# PCB.net
KiCad netlist of a schematic drawn in EAGLE
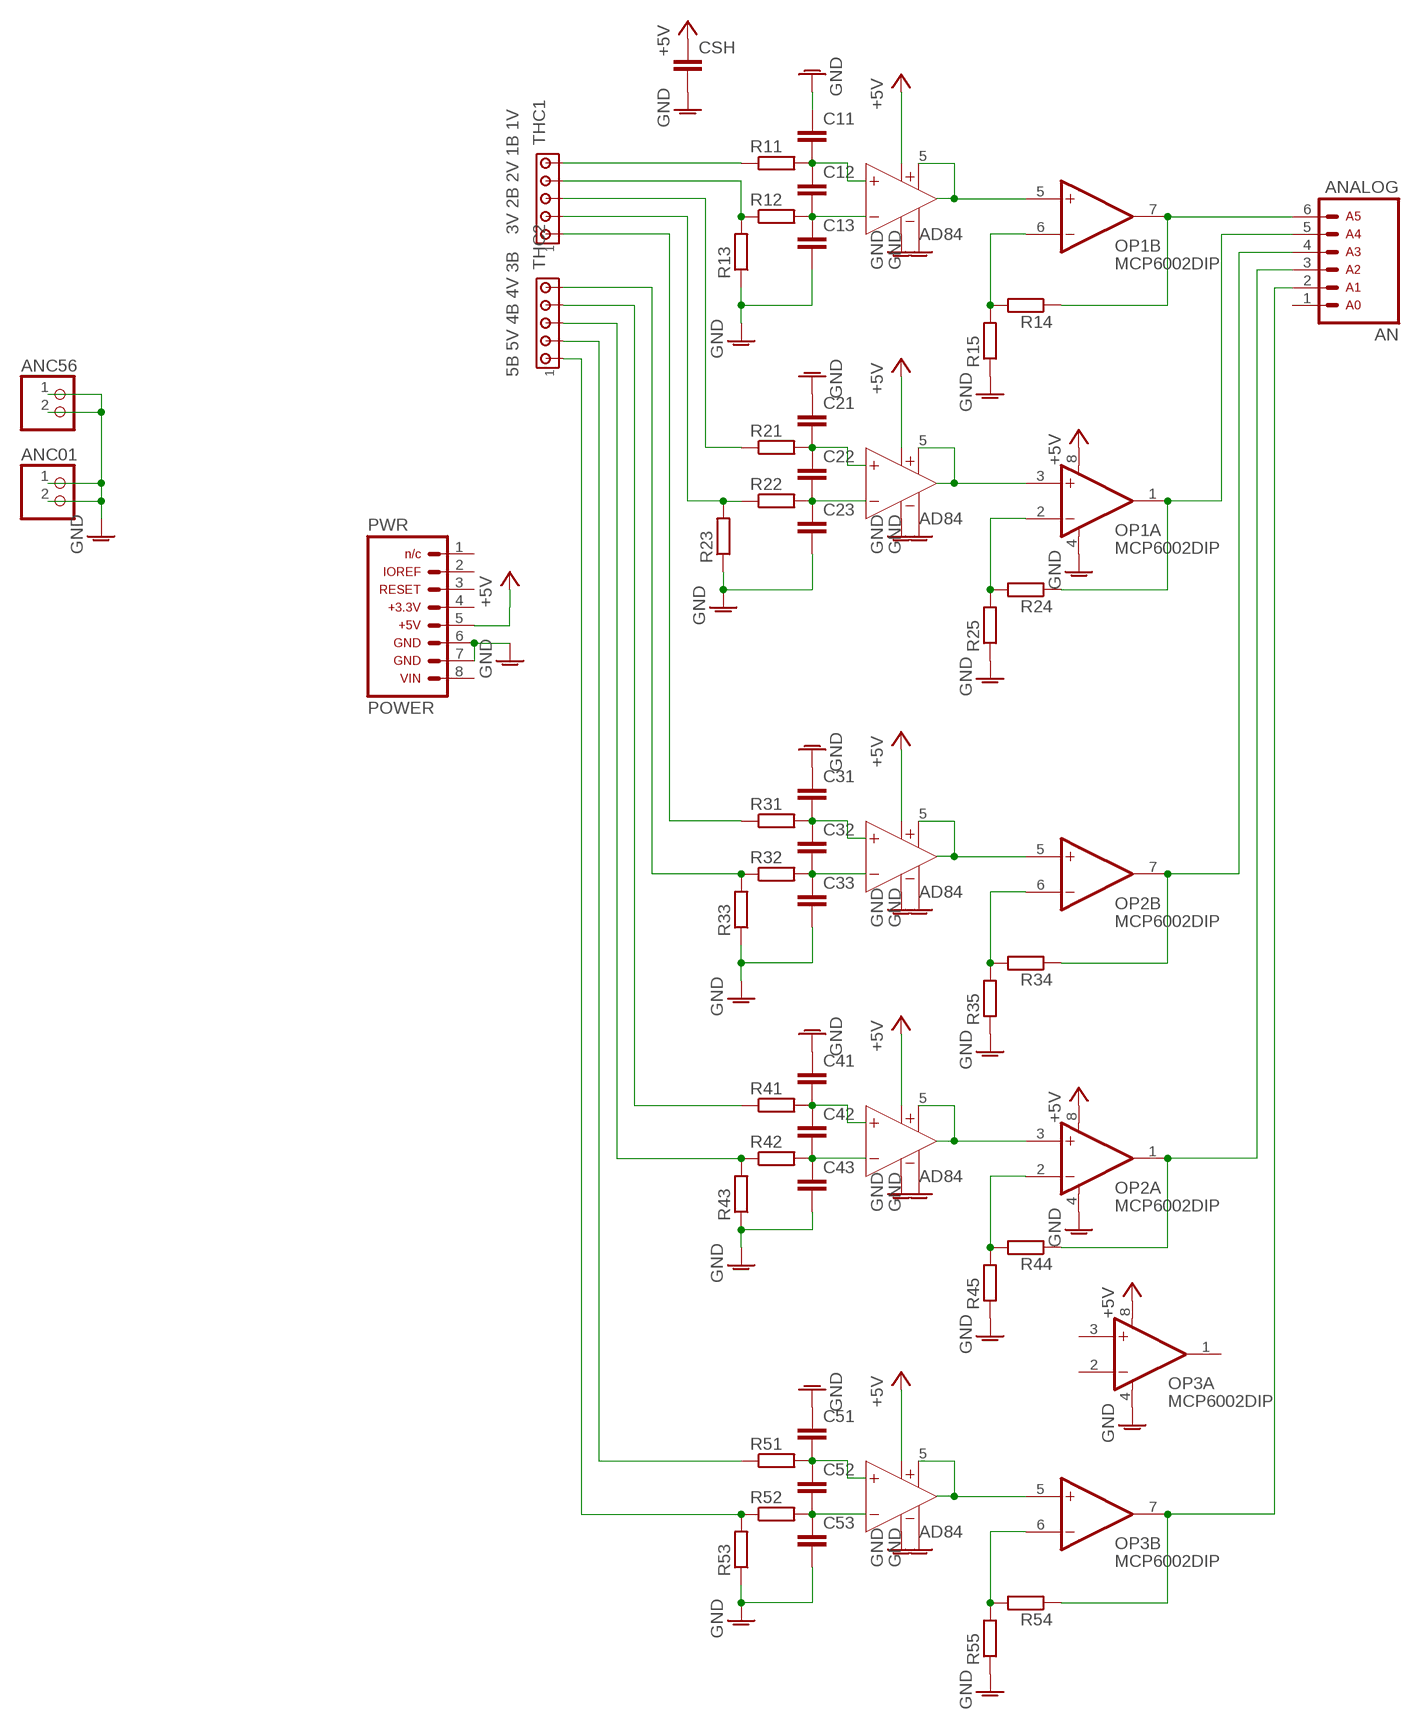
[diagram p0: schematic, sheet 1]

(export (version "E")
  (design (tool "Eeschema 10.0.6"))
  (components
    (comp (ref "AN")
      (value "ARDUINO_CONN-ANALOGSIP")
      (footprint "eagle-import:CONN-1X06")
      (libsource (lib "eagle-import") (part "ARDUINO_CONN-ANALOGSIP"))
    )
    (comp (ref "ANC01")
      (value "PINHD-1X2")
      (footprint "eagle-import:1X02")
      (libsource (lib "eagle-import") (part "PINHD-1X2"))
    )
    (comp (ref "ANC56")
      (value "PINHD-1X2")
      (footprint "eagle-import:1X02")
      (libsource (lib "eagle-import") (part "PINHD-1X2"))
    )
    (comp (ref "C11")
      (value "C-EU050-025X075")
      (footprint "eagle-import:C050-025X075")
      (libsource (lib "eagle-import") (part "C-EU050-025X075"))
    )
    (comp (ref "C12")
      (value "C-EU050-025X075")
      (footprint "eagle-import:C050-025X075")
      (libsource (lib "eagle-import") (part "C-EU050-025X075"))
    )
    (comp (ref "C13")
      (value "C-EU050-025X075")
      (footprint "eagle-import:C050-025X075")
      (libsource (lib "eagle-import") (part "C-EU050-025X075"))
    )
    (comp (ref "C21")
      (value "C-EU050-025X075")
      (footprint "eagle-import:C050-025X075")
      (libsource (lib "eagle-import") (part "C-EU050-025X075"))
    )
    (comp (ref "C22")
      (value "C-EU050-025X075")
      (footprint "eagle-import:C050-025X075")
      (libsource (lib "eagle-import") (part "C-EU050-025X075"))
    )
    (comp (ref "C23")
      (value "C-EU050-025X075")
      (footprint "eagle-import:C050-025X075")
      (libsource (lib "eagle-import") (part "C-EU050-025X075"))
    )
    (comp (ref "C31")
      (value "C-EU050-025X075")
      (footprint "eagle-import:C050-025X075")
      (libsource (lib "eagle-import") (part "C-EU050-025X075"))
    )
    (comp (ref "C32")
      (value "C-EU050-025X075")
      (footprint "eagle-import:C050-025X075")
      (libsource (lib "eagle-import") (part "C-EU050-025X075"))
    )
    (comp (ref "C33")
      (value "C-EU050-025X075")
      (footprint "eagle-import:C050-025X075")
      (libsource (lib "eagle-import") (part "C-EU050-025X075"))
    )
    (comp (ref "C41")
      (value "C-EU050-025X075")
      (footprint "eagle-import:C050-025X075")
      (libsource (lib "eagle-import") (part "C-EU050-025X075"))
    )
    (comp (ref "C42")
      (value "C-EU050-025X075")
      (footprint "eagle-import:C050-025X075")
      (libsource (lib "eagle-import") (part "C-EU050-025X075"))
    )
    (comp (ref "C43")
      (value "C-EU050-025X075")
      (footprint "eagle-import:C050-025X075")
      (libsource (lib "eagle-import") (part "C-EU050-025X075"))
    )
    (comp (ref "C51")
      (value "C-EU050-025X075")
      (footprint "eagle-import:C050-025X075")
      (libsource (lib "eagle-import") (part "C-EU050-025X075"))
    )
    (comp (ref "C52")
      (value "C-EU050-025X075")
      (footprint "eagle-import:C050-025X075")
      (libsource (lib "eagle-import") (part "C-EU050-025X075"))
    )
    (comp (ref "C53")
      (value "C-EU050-025X075")
      (footprint "eagle-import:C050-025X075")
      (libsource (lib "eagle-import") (part "C-EU050-025X075"))
    )
    (comp (ref "CSH")
      (value "C-EU050-025X075")
      (footprint "eagle-import:C050-025X075")
      (libsource (lib "eagle-import") (part "C-EU050-025X075"))
    )
    (comp (ref "OP1")
      (value "MCP6002DIP")
      (footprint "eagle-import:DIP-8")
      (libsource (lib "eagle-import") (part "MCP6002DIP"))
    )
    (comp (ref "OP2")
      (value "MCP6002DIP")
      (footprint "eagle-import:DIP-8")
      (libsource (lib "eagle-import") (part "MCP6002DIP"))
    )
    (comp (ref "OP3")
      (value "MCP6002DIP")
      (footprint "eagle-import:DIP-8")
      (libsource (lib "eagle-import") (part "MCP6002DIP"))
    )
    (comp (ref "PWR")
      (value "ARDUINO_CONN-POWERSIP")
      (footprint "eagle-import:CONN-1X08")
      (libsource (lib "eagle-import") (part "ARDUINO_CONN-POWERSIP"))
    )
    (comp (ref "R11")
      (value "R-EU_0207/10")
      (footprint "eagle-import:0207_10")
      (libsource (lib "eagle-import") (part "R-EU_0207/10"))
    )
    (comp (ref "R12")
      (value "R-EU_0207/10")
      (footprint "eagle-import:0207_10")
      (libsource (lib "eagle-import") (part "R-EU_0207/10"))
    )
    (comp (ref "R13")
      (value "R-EU_0207/10")
      (footprint "eagle-import:0207_10")
      (libsource (lib "eagle-import") (part "R-EU_0207/10"))
    )
    (comp (ref "R14")
      (value "R-EU_0207/10")
      (footprint "eagle-import:0207_10")
      (libsource (lib "eagle-import") (part "R-EU_0207/10"))
    )
    (comp (ref "R15")
      (value "R-EU_0207/10")
      (footprint "eagle-import:0207_10")
      (libsource (lib "eagle-import") (part "R-EU_0207/10"))
    )
    (comp (ref "R21")
      (value "R-EU_0207/10")
      (footprint "eagle-import:0207_10")
      (libsource (lib "eagle-import") (part "R-EU_0207/10"))
    )
    (comp (ref "R22")
      (value "R-EU_0207/10")
      (footprint "eagle-import:0207_10")
      (libsource (lib "eagle-import") (part "R-EU_0207/10"))
    )
    (comp (ref "R23")
      (value "R-EU_0207/10")
      (footprint "eagle-import:0207_10")
      (libsource (lib "eagle-import") (part "R-EU_0207/10"))
    )
    (comp (ref "R24")
      (value "R-EU_0207/10")
      (footprint "eagle-import:0207_10")
      (libsource (lib "eagle-import") (part "R-EU_0207/10"))
    )
    (comp (ref "R25")
      (value "R-EU_0207/10")
      (footprint "eagle-import:0207_10")
      (libsource (lib "eagle-import") (part "R-EU_0207/10"))
    )
    (comp (ref "R31")
      (value "R-EU_0207/10")
      (footprint "eagle-import:0207_10")
      (libsource (lib "eagle-import") (part "R-EU_0207/10"))
    )
    (comp (ref "R32")
      (value "R-EU_0207/10")
      (footprint "eagle-import:0207_10")
      (libsource (lib "eagle-import") (part "R-EU_0207/10"))
    )
    (comp (ref "R33")
      (value "R-EU_0207/10")
      (footprint "eagle-import:0207_10")
      (libsource (lib "eagle-import") (part "R-EU_0207/10"))
    )
    (comp (ref "R34")
      (value "R-EU_0207/10")
      (footprint "eagle-import:0207_10")
      (libsource (lib "eagle-import") (part "R-EU_0207/10"))
    )
    (comp (ref "R35")
      (value "R-EU_0207/10")
      (footprint "eagle-import:0207_10")
      (libsource (lib "eagle-import") (part "R-EU_0207/10"))
    )
    (comp (ref "R41")
      (value "R-EU_0207/10")
      (footprint "eagle-import:0207_10")
      (libsource (lib "eagle-import") (part "R-EU_0207/10"))
    )
    (comp (ref "R42")
      (value "R-EU_0207/10")
      (footprint "eagle-import:0207_10")
      (libsource (lib "eagle-import") (part "R-EU_0207/10"))
    )
    (comp (ref "R43")
      (value "R-EU_0207/10")
      (footprint "eagle-import:0207_10")
      (libsource (lib "eagle-import") (part "R-EU_0207/10"))
    )
    (comp (ref "R44")
      (value "R-EU_0207/10")
      (footprint "eagle-import:0207_10")
      (libsource (lib "eagle-import") (part "R-EU_0207/10"))
    )
    (comp (ref "R45")
      (value "R-EU_0207/10")
      (footprint "eagle-import:0207_10")
      (libsource (lib "eagle-import") (part "R-EU_0207/10"))
    )
    (comp (ref "R51")
      (value "R-EU_0207/10")
      (footprint "eagle-import:0207_10")
      (libsource (lib "eagle-import") (part "R-EU_0207/10"))
    )
    (comp (ref "R52")
      (value "R-EU_0207/10")
      (footprint "eagle-import:0207_10")
      (libsource (lib "eagle-import") (part "R-EU_0207/10"))
    )
    (comp (ref "R53")
      (value "R-EU_0207/10")
      (footprint "eagle-import:0207_10")
      (libsource (lib "eagle-import") (part "R-EU_0207/10"))
    )
    (comp (ref "R54")
      (value "R-EU_0207/10")
      (footprint "eagle-import:0207_10")
      (libsource (lib "eagle-import") (part "R-EU_0207/10"))
    )
    (comp (ref "R55")
      (value "R-EU_0207/10")
      (footprint "eagle-import:0207_10")
      (libsource (lib "eagle-import") (part "R-EU_0207/10"))
    )
    (comp (ref "THC1")
      (value "3V 2B 2V 1B 1V")
      (footprint "eagle-import:10X05MTA")
      (libsource (lib "eagle-import") (part "MTA05-100"))
    )
    (comp (ref "THC2")
      (value "5B 5V 4B 4V 3B")
      (footprint "eagle-import:10X05MTA")
      (libsource (lib "eagle-import") (part "MTA05-100"))
    )
    (comp (ref "U$1")
      (value "AD84")
      (footprint "eagle-import:DIP-8")
      (libsource (lib "eagle-import") (part "AD84"))
    )
    (comp (ref "U$2")
      (value "AD84")
      (footprint "eagle-import:DIP-8")
      (libsource (lib "eagle-import") (part "AD84"))
    )
    (comp (ref "U$3")
      (value "AD84")
      (footprint "eagle-import:DIP-8")
      (libsource (lib "eagle-import") (part "AD84"))
    )
    (comp (ref "U$4")
      (value "AD84")
      (footprint "eagle-import:DIP-8")
      (libsource (lib "eagle-import") (part "AD84"))
    )
    (comp (ref "U$5")
      (value "AD84")
      (footprint "eagle-import:DIP-8")
      (libsource (lib "eagle-import") (part "AD84"))
    )
  )
  (nets
    (net (code "1") (name "+5V") (class "Default")
      (node (ref "CSH") (pin "1") (pinfunction "1_1") (pintype "passive"))
      (node (ref "OP1") (pin "8") (pinfunction "V+_8") (pintype "power_in"))
      (node (ref "OP2") (pin "8") (pinfunction "V+_8") (pintype "power_in"))
      (node (ref "OP3") (pin "8") (pinfunction "V+_8") (pintype "power_in"))
      (node (ref "PWR") (pin "5") (pinfunction "5_5") (pintype "passive"))
      (node (ref "U$1") (pin "7") (pinfunction "V+_7") (pintype "power_in"))
      (node (ref "U$2") (pin "7") (pinfunction "V+_7") (pintype "power_in"))
      (node (ref "U$3") (pin "7") (pinfunction "V+_7") (pintype "power_in"))
      (node (ref "U$4") (pin "7") (pinfunction "V+_7") (pintype "power_in"))
      (node (ref "U$5") (pin "7") (pinfunction "V+_7") (pintype "power_in"))
    )
    (net (code "2") (name "GND") (class "Default")
      (node (ref "ANC01") (pin "1") (pinfunction "1_1") (pintype "passive"))
      (node (ref "ANC01") (pin "2") (pinfunction "2_2") (pintype "passive"))
      (node (ref "ANC56") (pin "1") (pinfunction "1_1") (pintype "passive"))
      (node (ref "ANC56") (pin "2") (pinfunction "2_2") (pintype "passive"))
      (node (ref "C11") (pin "1") (pinfunction "1_1") (pintype "passive"))
      (node (ref "C13") (pin "2") (pinfunction "2_2") (pintype "passive"))
      (node (ref "C21") (pin "1") (pinfunction "1_1") (pintype "passive"))
      (node (ref "C23") (pin "2") (pinfunction "2_2") (pintype "passive"))
      (node (ref "C31") (pin "1") (pinfunction "1_1") (pintype "passive"))
      (node (ref "C33") (pin "2") (pinfunction "2_2") (pintype "passive"))
      (node (ref "C41") (pin "1") (pinfunction "1_1") (pintype "passive"))
      (node (ref "C43") (pin "2") (pinfunction "2_2") (pintype "passive"))
      (node (ref "C51") (pin "1") (pinfunction "1_1") (pintype "passive"))
      (node (ref "C53") (pin "2") (pinfunction "2_2") (pintype "passive"))
      (node (ref "CSH") (pin "2") (pinfunction "2_2") (pintype "passive"))
      (node (ref "OP1") (pin "4") (pinfunction "V-_4") (pintype "power_in"))
      (node (ref "OP2") (pin "4") (pinfunction "V-_4") (pintype "power_in"))
      (node (ref "OP3") (pin "4") (pinfunction "V-_4") (pintype "power_in"))
      (node (ref "PWR") (pin "6") (pinfunction "6_6") (pintype "passive"))
      (node (ref "PWR") (pin "7") (pinfunction "7_7") (pintype "passive"))
      (node (ref "R13") (pin "1") (pinfunction "1_1") (pintype "passive"))
      (node (ref "R15") (pin "1") (pinfunction "1_1") (pintype "passive"))
      (node (ref "R23") (pin "1") (pinfunction "1_1") (pintype "passive"))
      (node (ref "R25") (pin "1") (pinfunction "1_1") (pintype "passive"))
      (node (ref "R33") (pin "1") (pinfunction "1_1") (pintype "passive"))
      (node (ref "R35") (pin "1") (pinfunction "1_1") (pintype "passive"))
      (node (ref "R43") (pin "1") (pinfunction "1_1") (pintype "passive"))
      (node (ref "R45") (pin "1") (pinfunction "1_1") (pintype "passive"))
      (node (ref "R53") (pin "1") (pinfunction "1_1") (pintype "passive"))
      (node (ref "R55") (pin "1") (pinfunction "1_1") (pintype "passive"))
      (node (ref "U$1") (pin "2") (pinfunction "REF_2") (pintype "passive"))
      (node (ref "U$1") (pin "3") (pinfunction "V-_3") (pintype "power_in"))
      (node (ref "U$2") (pin "2") (pinfunction "REF_2") (pintype "passive"))
      (node (ref "U$2") (pin "3") (pinfunction "V-_3") (pintype "power_in"))
      (node (ref "U$3") (pin "2") (pinfunction "REF_2") (pintype "passive"))
      (node (ref "U$3") (pin "3") (pinfunction "V-_3") (pintype "power_in"))
      (node (ref "U$4") (pin "2") (pinfunction "REF_2") (pintype "passive"))
      (node (ref "U$4") (pin "3") (pinfunction "V-_3") (pintype "power_in"))
      (node (ref "U$5") (pin "2") (pinfunction "REF_2") (pintype "passive"))
      (node (ref "U$5") (pin "3") (pinfunction "V-_3") (pintype "power_in"))
    )
    (net (code "3") (name "Net-(OP1A-+IN)") (class "Default")
      (node (ref "OP1") (pin "3") (pinfunction "+IN_3") (pintype "input"))
      (node (ref "U$2") (pin "5") (pinfunction "SENS_5") (pintype "output"))
      (node (ref "U$2") (pin "6") (pinfunction "OUT_6") (pintype "output"))
    )
    (net (code "4") (name "Net-(OP1A--IN)") (class "Default")
      (node (ref "OP1") (pin "2") (pinfunction "-IN_2") (pintype "input"))
      (node (ref "R24") (pin "2") (pinfunction "2_2") (pintype "passive"))
      (node (ref "R25") (pin "2") (pinfunction "2_2") (pintype "passive"))
    )
    (net (code "5") (name "Net-(OP1A-OUT)") (class "Default")
      (node (ref "AN") (pin "5") (pinfunction "5_5") (pintype "passive"))
      (node (ref "OP1") (pin "1") (pinfunction "OUT_1") (pintype "output"))
      (node (ref "R24") (pin "1") (pinfunction "1_1") (pintype "passive"))
    )
    (net (code "6") (name "Net-(OP1B-+IN)") (class "Default")
      (node (ref "OP1") (pin "5") (pinfunction "+IN_5") (pintype "input"))
      (node (ref "U$1") (pin "5") (pinfunction "SENS_5") (pintype "output"))
      (node (ref "U$1") (pin "6") (pinfunction "OUT_6") (pintype "output"))
    )
    (net (code "7") (name "Net-(OP1B--IN)") (class "Default")
      (node (ref "OP1") (pin "6") (pinfunction "-IN_6") (pintype "input"))
      (node (ref "R14") (pin "2") (pinfunction "2_2") (pintype "passive"))
      (node (ref "R15") (pin "2") (pinfunction "2_2") (pintype "passive"))
    )
    (net (code "8") (name "Net-(OP1B-OUT)") (class "Default")
      (node (ref "AN") (pin "6") (pinfunction "6_6") (pintype "passive"))
      (node (ref "OP1") (pin "7") (pinfunction "OUT_7") (pintype "output"))
      (node (ref "R14") (pin "1") (pinfunction "1_1") (pintype "passive"))
    )
    (net (code "9") (name "Net-(OP2A-+IN)") (class "Default")
      (node (ref "OP2") (pin "3") (pinfunction "+IN_3") (pintype "input"))
      (node (ref "U$4") (pin "5") (pinfunction "SENS_5") (pintype "output"))
      (node (ref "U$4") (pin "6") (pinfunction "OUT_6") (pintype "output"))
    )
    (net (code "10") (name "Net-(OP2A--IN)") (class "Default")
      (node (ref "OP2") (pin "2") (pinfunction "-IN_2") (pintype "input"))
      (node (ref "R44") (pin "2") (pinfunction "2_2") (pintype "passive"))
      (node (ref "R45") (pin "2") (pinfunction "2_2") (pintype "passive"))
    )
    (net (code "11") (name "Net-(OP2A-OUT)") (class "Default")
      (node (ref "AN") (pin "3") (pinfunction "3_3") (pintype "passive"))
      (node (ref "OP2") (pin "1") (pinfunction "OUT_1") (pintype "output"))
      (node (ref "R44") (pin "1") (pinfunction "1_1") (pintype "passive"))
    )
    (net (code "12") (name "Net-(OP2B-+IN)") (class "Default")
      (node (ref "OP2") (pin "5") (pinfunction "+IN_5") (pintype "input"))
      (node (ref "U$3") (pin "5") (pinfunction "SENS_5") (pintype "output"))
      (node (ref "U$3") (pin "6") (pinfunction "OUT_6") (pintype "output"))
    )
    (net (code "13") (name "Net-(OP2B--IN)") (class "Default")
      (node (ref "OP2") (pin "6") (pinfunction "-IN_6") (pintype "input"))
      (node (ref "R34") (pin "2") (pinfunction "2_2") (pintype "passive"))
      (node (ref "R35") (pin "2") (pinfunction "2_2") (pintype "passive"))
    )
    (net (code "14") (name "Net-(OP2B-OUT)") (class "Default")
      (node (ref "AN") (pin "4") (pinfunction "4_4") (pintype "passive"))
      (node (ref "OP2") (pin "7") (pinfunction "OUT_7") (pintype "output"))
      (node (ref "R34") (pin "1") (pinfunction "1_1") (pintype "passive"))
    )
    (net (code "15") (name "Net-(OP3B-+IN)") (class "Default")
      (node (ref "OP3") (pin "5") (pinfunction "+IN_5") (pintype "input"))
      (node (ref "U$5") (pin "5") (pinfunction "SENS_5") (pintype "output"))
      (node (ref "U$5") (pin "6") (pinfunction "OUT_6") (pintype "output"))
    )
    (net (code "16") (name "Net-(OP3B--IN)") (class "Default")
      (node (ref "OP3") (pin "6") (pinfunction "-IN_6") (pintype "input"))
      (node (ref "R54") (pin "2") (pinfunction "2_2") (pintype "passive"))
      (node (ref "R55") (pin "2") (pinfunction "2_2") (pintype "passive"))
    )
    (net (code "17") (name "Net-(OP3B-OUT)") (class "Default")
      (node (ref "AN") (pin "2") (pinfunction "2_2") (pintype "passive"))
      (node (ref "OP3") (pin "7") (pinfunction "OUT_7") (pintype "output"))
      (node (ref "R54") (pin "1") (pinfunction "1_1") (pintype "passive"))
    )
    (net (code "18") (name "Net-(R11-Pad1)") (class "Default")
      (node (ref "R11") (pin "1") (pinfunction "1_1") (pintype "passive"))
      (node (ref "THC1") (pin "5") (pinfunction "5_5") (pintype "passive"))
    )
    (net (code "19") (name "Net-(R12-Pad1)") (class "Default")
      (node (ref "R12") (pin "1") (pinfunction "1_1") (pintype "passive"))
      (node (ref "R13") (pin "2") (pinfunction "2_2") (pintype "passive"))
      (node (ref "THC1") (pin "4") (pinfunction "4_4") (pintype "passive"))
    )
    (net (code "20") (name "Net-(R21-Pad1)") (class "Default")
      (node (ref "R21") (pin "1") (pinfunction "1_1") (pintype "passive"))
      (node (ref "THC1") (pin "3") (pinfunction "3_3") (pintype "passive"))
    )
    (net (code "21") (name "Net-(R22-Pad1)") (class "Default")
      (node (ref "R22") (pin "1") (pinfunction "1_1") (pintype "passive"))
      (node (ref "R23") (pin "2") (pinfunction "2_2") (pintype "passive"))
      (node (ref "THC1") (pin "2") (pinfunction "2_2") (pintype "passive"))
    )
    (net (code "22") (name "Net-(R31-Pad1)") (class "Default")
      (node (ref "R31") (pin "1") (pinfunction "1_1") (pintype "passive"))
      (node (ref "THC1") (pin "1") (pinfunction "1_1") (pintype "passive"))
    )
    (net (code "23") (name "Net-(R32-Pad1)") (class "Default")
      (node (ref "R32") (pin "1") (pinfunction "1_1") (pintype "passive"))
      (node (ref "R33") (pin "2") (pinfunction "2_2") (pintype "passive"))
      (node (ref "THC2") (pin "5") (pinfunction "5_5") (pintype "passive"))
    )
    (net (code "24") (name "Net-(R41-Pad1)") (class "Default")
      (node (ref "R41") (pin "1") (pinfunction "1_1") (pintype "passive"))
      (node (ref "THC2") (pin "4") (pinfunction "4_4") (pintype "passive"))
    )
    (net (code "25") (name "Net-(R42-Pad1)") (class "Default")
      (node (ref "R42") (pin "1") (pinfunction "1_1") (pintype "passive"))
      (node (ref "R43") (pin "2") (pinfunction "2_2") (pintype "passive"))
      (node (ref "THC2") (pin "3") (pinfunction "3_3") (pintype "passive"))
    )
    (net (code "26") (name "Net-(R51-Pad1)") (class "Default")
      (node (ref "R51") (pin "1") (pinfunction "1_1") (pintype "passive"))
      (node (ref "THC2") (pin "2") (pinfunction "2_2") (pintype "passive"))
    )
    (net (code "27") (name "Net-(R52-Pad1)") (class "Default")
      (node (ref "R52") (pin "1") (pinfunction "1_1") (pintype "passive"))
      (node (ref "R53") (pin "2") (pinfunction "2_2") (pintype "passive"))
      (node (ref "THC2") (pin "1") (pinfunction "1_1") (pintype "passive"))
    )
    (net (code "28") (name "Net-(U$1-IN+)") (class "Default")
      (node (ref "C11") (pin "2") (pinfunction "2_2") (pintype "passive"))
      (node (ref "C12") (pin "1") (pinfunction "1_1") (pintype "passive"))
      (node (ref "R11") (pin "2") (pinfunction "2_2") (pintype "passive"))
      (node (ref "U$1") (pin "8") (pinfunction "IN+_8") (pintype "input"))
    )
    (net (code "29") (name "Net-(U$1-IN-)") (class "Default")
      (node (ref "C12") (pin "2") (pinfunction "2_2") (pintype "passive"))
      (node (ref "C13") (pin "1") (pinfunction "1_1") (pintype "passive"))
      (node (ref "R12") (pin "2") (pinfunction "2_2") (pintype "passive"))
      (node (ref "U$1") (pin "1") (pinfunction "IN-_1") (pintype "input"))
    )
    (net (code "30") (name "Net-(U$2-IN+)") (class "Default")
      (node (ref "C21") (pin "2") (pinfunction "2_2") (pintype "passive"))
      (node (ref "C22") (pin "1") (pinfunction "1_1") (pintype "passive"))
      (node (ref "R21") (pin "2") (pinfunction "2_2") (pintype "passive"))
      (node (ref "U$2") (pin "8") (pinfunction "IN+_8") (pintype "input"))
    )
    (net (code "31") (name "Net-(U$2-IN-)") (class "Default")
      (node (ref "C22") (pin "2") (pinfunction "2_2") (pintype "passive"))
      (node (ref "C23") (pin "1") (pinfunction "1_1") (pintype "passive"))
      (node (ref "R22") (pin "2") (pinfunction "2_2") (pintype "passive"))
      (node (ref "U$2") (pin "1") (pinfunction "IN-_1") (pintype "input"))
    )
    (net (code "32") (name "Net-(U$3-IN+)") (class "Default")
      (node (ref "C31") (pin "2") (pinfunction "2_2") (pintype "passive"))
      (node (ref "C32") (pin "1") (pinfunction "1_1") (pintype "passive"))
      (node (ref "R31") (pin "2") (pinfunction "2_2") (pintype "passive"))
      (node (ref "U$3") (pin "8") (pinfunction "IN+_8") (pintype "input"))
    )
    (net (code "33") (name "Net-(U$3-IN-)") (class "Default")
      (node (ref "C32") (pin "2") (pinfunction "2_2") (pintype "passive"))
      (node (ref "C33") (pin "1") (pinfunction "1_1") (pintype "passive"))
      (node (ref "R32") (pin "2") (pinfunction "2_2") (pintype "passive"))
      (node (ref "U$3") (pin "1") (pinfunction "IN-_1") (pintype "input"))
    )
    (net (code "34") (name "Net-(U$4-IN+)") (class "Default")
      (node (ref "C41") (pin "2") (pinfunction "2_2") (pintype "passive"))
      (node (ref "C42") (pin "1") (pinfunction "1_1") (pintype "passive"))
      (node (ref "R41") (pin "2") (pinfunction "2_2") (pintype "passive"))
      (node (ref "U$4") (pin "8") (pinfunction "IN+_8") (pintype "input"))
    )
    (net (code "35") (name "Net-(U$4-IN-)") (class "Default")
      (node (ref "C42") (pin "2") (pinfunction "2_2") (pintype "passive"))
      (node (ref "C43") (pin "1") (pinfunction "1_1") (pintype "passive"))
      (node (ref "R42") (pin "2") (pinfunction "2_2") (pintype "passive"))
      (node (ref "U$4") (pin "1") (pinfunction "IN-_1") (pintype "input"))
    )
    (net (code "36") (name "Net-(U$5-IN+)") (class "Default")
      (node (ref "C51") (pin "2") (pinfunction "2_2") (pintype "passive"))
      (node (ref "C52") (pin "1") (pinfunction "1_1") (pintype "passive"))
      (node (ref "R51") (pin "2") (pinfunction "2_2") (pintype "passive"))
      (node (ref "U$5") (pin "8") (pinfunction "IN+_8") (pintype "input"))
    )
    (net (code "37") (name "Net-(U$5-IN-)") (class "Default")
      (node (ref "C52") (pin "2") (pinfunction "2_2") (pintype "passive"))
      (node (ref "C53") (pin "1") (pinfunction "1_1") (pintype "passive"))
      (node (ref "R52") (pin "2") (pinfunction "2_2") (pintype "passive"))
      (node (ref "U$5") (pin "1") (pinfunction "IN-_1") (pintype "input"))
    )
    (net (code "38") (name "unconnected-(AN-Pad1)") (class "Default")
      (node (ref "AN") (pin "1") (pinfunction "1_1") (pintype "passive"))
    )
    (net (code "39") (name "unconnected-(OP3A-+IN-Pad3)") (class "Default")
      (node (ref "OP3") (pin "3") (pinfunction "+IN_3") (pintype "input"))
    )
    (net (code "40") (name "unconnected-(OP3A--IN-Pad2)") (class "Default")
      (node (ref "OP3") (pin "2") (pinfunction "-IN_2") (pintype "input"))
    )
    (net (code "41") (name "unconnected-(OP3A-OUT-Pad1)") (class "Default")
      (node (ref "OP3") (pin "1") (pinfunction "OUT_1") (pintype "output"))
    )
    (net (code "42") (name "unconnected-(PWR-Pad1)") (class "Default")
      (node (ref "PWR") (pin "1") (pinfunction "1_1") (pintype "passive"))
    )
    (net (code "43") (name "unconnected-(PWR-Pad2)") (class "Default")
      (node (ref "PWR") (pin "2") (pinfunction "2_2") (pintype "passive"))
    )
    (net (code "44") (name "unconnected-(PWR-Pad3)") (class "Default")
      (node (ref "PWR") (pin "3") (pinfunction "3_3") (pintype "passive"))
    )
    (net (code "45") (name "unconnected-(PWR-Pad4)") (class "Default")
      (node (ref "PWR") (pin "4") (pinfunction "4_4") (pintype "passive"))
    )
    (net (code "46") (name "unconnected-(PWR-Pad8)") (class "Default")
      (node (ref "PWR") (pin "8") (pinfunction "8_8") (pintype "passive"))
    )
  )
)
